# IZU2023_computerboard_ver2.net
KiCad netlist of a schematic drawn in EAGLE
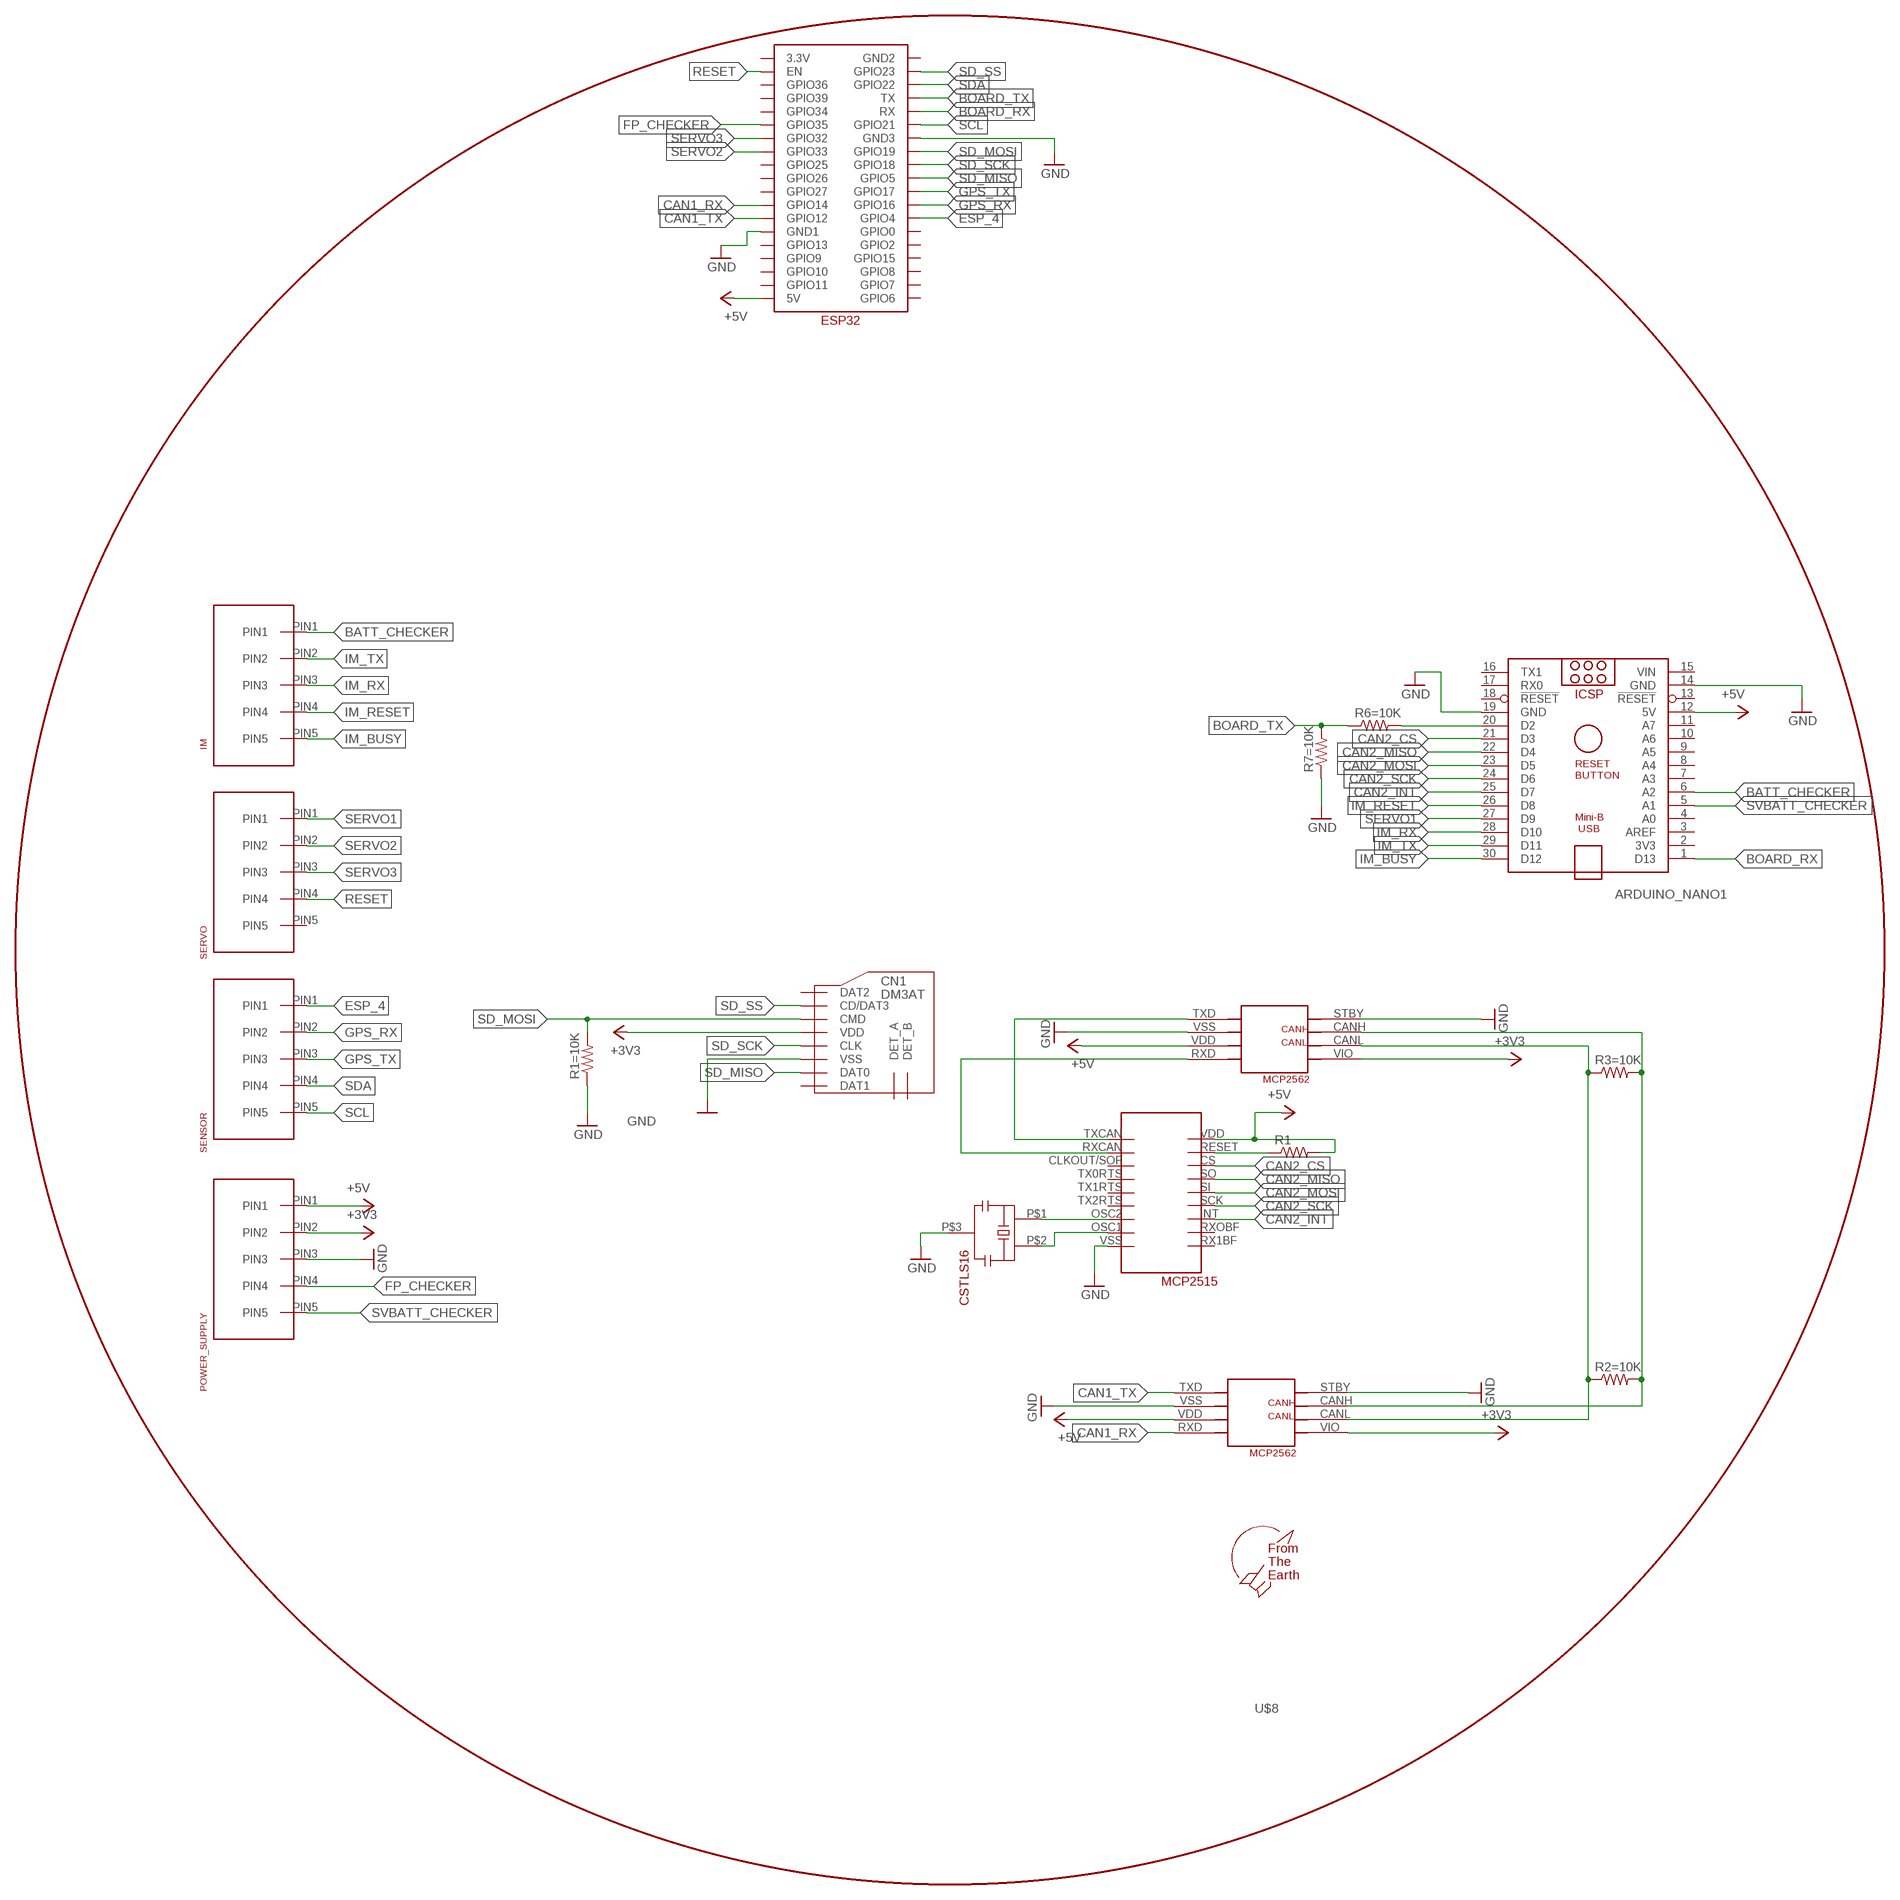
[diagram p0: schematic, sheet 1]

(export (version "E")
  (design (tool "Eeschema 10.0.6"))
  (components
    (comp (ref "ARDUINO_NANO1")
      (value "ARDUINO_NANO")
      (footprint "eagle-import:ARDUINO_NANO")
      (libsource (lib "eagle-import") (part "ARDUINO_NANO"))
    )
    (comp (ref "CN1")
      (value "DM3AT")
      (footprint "eagle-import:DM3AT")
      (libsource (lib "eagle-import") (part "DM3AT"))
    )
    (comp (ref "IM")
      (value "5PIN")
      (footprint "eagle-import:5PIN")
      (libsource (lib "eagle-import") (part "5PIN"))
    )
    (comp (ref "POWER_SUPPLY")
      (value "5PIN")
      (footprint "eagle-import:5PIN")
      (libsource (lib "eagle-import") (part "5PIN"))
    )
    (comp (ref "R1")
      (value "R-US_0204/7")
      (footprint "eagle-import:0204_7")
      (libsource (lib "eagle-import") (part "R-US_0204/7"))
    )
    (comp (ref "R1=10K")
      (value "R-US_0204/7")
      (footprint "eagle-import:0204_7")
      (libsource (lib "eagle-import") (part "R-US_0204/7"))
    )
    (comp (ref "R2=10K")
      (value "R-US_0204/7")
      (footprint "eagle-import:0204_7")
      (libsource (lib "eagle-import") (part "R-US_0204/7"))
    )
    (comp (ref "R3=10K")
      (value "R-US_0204/7")
      (footprint "eagle-import:0204_7")
      (libsource (lib "eagle-import") (part "R-US_0204/7"))
    )
    (comp (ref "R6=10K")
      (value "R-US_0204/7")
      (footprint "eagle-import:0204_7")
      (libsource (lib "eagle-import") (part "R-US_0204/7"))
    )
    (comp (ref "R7=10K")
      (value "R-US_0204/7")
      (footprint "eagle-import:0204_7")
      (libsource (lib "eagle-import") (part "R-US_0204/7"))
    )
    (comp (ref "SENSOR")
      (value "5PIN")
      (footprint "eagle-import:5PIN")
      (libsource (lib "eagle-import") (part "5PIN"))
    )
    (comp (ref "SERVO")
      (value "5PIN")
      (footprint "eagle-import:5PIN")
      (libsource (lib "eagle-import") (part "5PIN"))
    )
    (comp (ref "U$2")
      (value "MCP2515")
      (footprint "eagle-import:MCP2515")
      (libsource (lib "eagle-import") (part "MCP2515"))
    )
    (comp (ref "U$3")
      (value "MCP2562")
      (footprint "eagle-import:MCP2562")
      (libsource (lib "eagle-import") (part "MCP2562"))
    )
    (comp (ref "U$4")
      (value "MCP2562")
      (footprint "eagle-import:MCP2562")
      (libsource (lib "eagle-import") (part "MCP2562"))
    )
    (comp (ref "U$5")
      (value "CSTLS16")
      (footprint "eagle-import:CSTLS16")
      (libsource (lib "eagle-import") (part "CSTLS16"))
    )
    (comp (ref "U$7")
      (value "ESP32_ESP32")
      (footprint "eagle-import:ESP32_ESP32")
      (libsource (lib "eagle-import") (part "ESP32_ESP32"))
    )
    (comp (ref "U$8")
      (value "F.T.E.LOGO")
      (footprint "eagle-import:LOGO")
      (libsource (lib "eagle-import") (part "F.T.E.LOGO"))
    )
  )
  (nets
    (net (code "1") (name "+3V3") (class "Default")
      (node (ref "CN1") (pin "VDD") (pinfunction "VDD_VDD") (pintype "bidirectional"))
      (node (ref "POWER_SUPPLY") (pin "PIN2") (pinfunction "PIN2_PIN2") (pintype "bidirectional"))
      (node (ref "U$3") (pin "VIO") (pinfunction "VIO_VIO") (pintype "bidirectional"))
      (node (ref "U$4") (pin "VIO") (pinfunction "VIO_VIO") (pintype "bidirectional"))
    )
    (net (code "2") (name "+5V") (class "Default")
      (node (ref "ARDUINO_NANO1") (pin "12") (pinfunction "5V_12") (pintype "power_in"))
      (node (ref "POWER_SUPPLY") (pin "PIN1") (pinfunction "PIN1_PIN1") (pintype "bidirectional"))
      (node (ref "R1") (pin "2") (pinfunction "2_2") (pintype "passive"))
      (node (ref "U$2") (pin "VDD") (pinfunction "VDD_VDD") (pintype "bidirectional"))
      (node (ref "U$3") (pin "VDD") (pinfunction "VDD_VDD") (pintype "bidirectional"))
      (node (ref "U$4") (pin "VDD") (pinfunction "VDD_VDD") (pintype "bidirectional"))
      (node (ref "U$7") (pin "5V") (pinfunction "5V_5V") (pintype "bidirectional"))
    )
    (net (code "3") (name "/VIN") (class "Default")
      (node (ref "ARDUINO_NANO1") (pin "15") (pinfunction "VIN_15") (pintype "power_in"))
    )
    (net (code "4") (name "BATT_CHECKER") (class "Default")
      (node (ref "ARDUINO_NANO1") (pin "6") (pinfunction "A2_6") (pintype "bidirectional"))
      (node (ref "IM") (pin "PIN1") (pinfunction "PIN1_PIN1") (pintype "bidirectional"))
    )
    (net (code "5") (name "BOARD_RX") (class "Default")
      (node (ref "ARDUINO_NANO1") (pin "1") (pinfunction "D13_1") (pintype "bidirectional"))
      (node (ref "U$7") (pin "RX") (pinfunction "RX_RX") (pintype "bidirectional"))
    )
    (net (code "6") (name "BOARD_TX") (class "Default")
      (node (ref "R6=10K") (pin "1") (pinfunction "1_1") (pintype "passive"))
      (node (ref "R7=10K") (pin "2") (pinfunction "2_2") (pintype "passive"))
      (node (ref "U$7") (pin "TX") (pinfunction "TX_TX") (pintype "bidirectional"))
    )
    (net (code "7") (name "CAN1_RX") (class "Default")
      (node (ref "U$3") (pin "RXD") (pinfunction "RXD_RXD") (pintype "bidirectional"))
      (node (ref "U$7") (pin "GPIO14") (pinfunction "GPIO14_GPIO14") (pintype "bidirectional"))
    )
    (net (code "8") (name "CAN1_TX") (class "Default")
      (node (ref "U$3") (pin "TXD") (pinfunction "TXD_TXD") (pintype "bidirectional"))
      (node (ref "U$7") (pin "GPIO12") (pinfunction "GPIO12_GPIO12") (pintype "bidirectional"))
    )
    (net (code "9") (name "CAN2_CS") (class "Default")
      (node (ref "ARDUINO_NANO1") (pin "21") (pinfunction "D3_21") (pintype "bidirectional"))
      (node (ref "U$2") (pin "CS") (pinfunction "CS_CS") (pintype "bidirectional"))
    )
    (net (code "10") (name "CAN2_INT") (class "Default")
      (node (ref "ARDUINO_NANO1") (pin "25") (pinfunction "D7_25") (pintype "bidirectional"))
      (node (ref "U$2") (pin "INT") (pinfunction "INT_INT") (pintype "bidirectional"))
    )
    (net (code "11") (name "CAN2_MISO") (class "Default")
      (node (ref "ARDUINO_NANO1") (pin "22") (pinfunction "D4_22") (pintype "bidirectional"))
      (node (ref "U$2") (pin "SO") (pinfunction "SO_SO") (pintype "bidirectional"))
    )
    (net (code "12") (name "CAN2_MOSI") (class "Default")
      (node (ref "ARDUINO_NANO1") (pin "23") (pinfunction "D5_23") (pintype "bidirectional"))
      (node (ref "U$2") (pin "SI") (pinfunction "SI_SI") (pintype "bidirectional"))
    )
    (net (code "13") (name "CAN2_SCK") (class "Default")
      (node (ref "ARDUINO_NANO1") (pin "24") (pinfunction "D6_24") (pintype "bidirectional"))
      (node (ref "U$2") (pin "SCK") (pinfunction "SCK_SCK") (pintype "bidirectional"))
    )
    (net (code "14") (name "ESP_4") (class "Default")
      (node (ref "SENSOR") (pin "PIN1") (pinfunction "PIN1_PIN1") (pintype "bidirectional"))
      (node (ref "U$7") (pin "GPIO4") (pinfunction "GPIO4_GPIO4") (pintype "bidirectional"))
    )
    (net (code "15") (name "FP_CHECKER") (class "Default")
      (node (ref "POWER_SUPPLY") (pin "PIN4") (pinfunction "PIN4_PIN4") (pintype "bidirectional"))
      (node (ref "U$7") (pin "GPIO35") (pinfunction "GPIO35_GPIO35") (pintype "bidirectional"))
    )
    (net (code "16") (name "GND") (class "Default")
      (node (ref "ARDUINO_NANO1") (pin "14") (pinfunction "GND_14") (pintype "power_in"))
      (node (ref "ARDUINO_NANO1") (pin "19") (pinfunction "GND_19") (pintype "power_in"))
      (node (ref "CN1") (pin "VSS") (pinfunction "VSS_VSS") (pintype "bidirectional"))
      (node (ref "POWER_SUPPLY") (pin "PIN3") (pinfunction "PIN3_PIN3") (pintype "bidirectional"))
      (node (ref "R1=10K") (pin "1") (pinfunction "1_1") (pintype "passive"))
      (node (ref "R7=10K") (pin "1") (pinfunction "1_1") (pintype "passive"))
      (node (ref "U$2") (pin "VSS") (pinfunction "VSS_VSS") (pintype "bidirectional"))
      (node (ref "U$3") (pin "STBY") (pinfunction "STBY_STBY") (pintype "bidirectional"))
      (node (ref "U$3") (pin "VSS") (pinfunction "VSS_VSS") (pintype "bidirectional"))
      (node (ref "U$4") (pin "STBY") (pinfunction "STBY_STBY") (pintype "bidirectional"))
      (node (ref "U$4") (pin "VSS") (pinfunction "VSS_VSS") (pintype "bidirectional"))
      (node (ref "U$5") (pin "P$3") (pinfunction "P$3_P$3") (pintype "bidirectional"))
      (node (ref "U$7") (pin "GND1") (pinfunction "GND1_GND1") (pintype "bidirectional"))
      (node (ref "U$7") (pin "GND3") (pinfunction "GND3_GND3") (pintype "bidirectional"))
    )
    (net (code "17") (name "GPS_RX") (class "Default")
      (node (ref "SENSOR") (pin "PIN2") (pinfunction "PIN2_PIN2") (pintype "bidirectional"))
      (node (ref "U$7") (pin "GPIO16") (pinfunction "GPIO16_GPIO16") (pintype "bidirectional"))
    )
    (net (code "18") (name "GPS_TX") (class "Default")
      (node (ref "SENSOR") (pin "PIN3") (pinfunction "PIN3_PIN3") (pintype "bidirectional"))
      (node (ref "U$7") (pin "GPIO17") (pinfunction "GPIO17_GPIO17") (pintype "bidirectional"))
    )
    (net (code "19") (name "IM_BUSY") (class "Default")
      (node (ref "ARDUINO_NANO1") (pin "30") (pinfunction "D12_30") (pintype "bidirectional"))
      (node (ref "IM") (pin "PIN5") (pinfunction "PIN5_PIN5") (pintype "bidirectional"))
    )
    (net (code "20") (name "IM_RESET") (class "Default")
      (node (ref "ARDUINO_NANO1") (pin "26") (pinfunction "D8_26") (pintype "bidirectional"))
      (node (ref "IM") (pin "PIN4") (pinfunction "PIN4_PIN4") (pintype "bidirectional"))
    )
    (net (code "21") (name "IM_RX") (class "Default")
      (node (ref "ARDUINO_NANO1") (pin "28") (pinfunction "D10_28") (pintype "bidirectional"))
      (node (ref "IM") (pin "PIN3") (pinfunction "PIN3_PIN3") (pintype "bidirectional"))
    )
    (net (code "22") (name "IM_TX") (class "Default")
      (node (ref "ARDUINO_NANO1") (pin "29") (pinfunction "D11_29") (pintype "bidirectional"))
      (node (ref "IM") (pin "PIN2") (pinfunction "PIN2_PIN2") (pintype "bidirectional"))
    )
    (net (code "23") (name "Net-(ARDUINO_NANO1-D2)") (class "Default")
      (node (ref "ARDUINO_NANO1") (pin "20") (pinfunction "D2_20") (pintype "bidirectional"))
      (node (ref "R6=10K") (pin "2") (pinfunction "2_2") (pintype "passive"))
    )
    (net (code "24") (name "Net-(R1-Pad1)") (class "Default")
      (node (ref "R1") (pin "1") (pinfunction "1_1") (pintype "passive"))
      (node (ref "U$2") (pin "RESET") (pinfunction "RESET_RESET") (pintype "bidirectional"))
    )
    (net (code "25") (name "Net-(R2=10K-Pad1)") (class "Default")
      (node (ref "R2=10K") (pin "1") (pinfunction "1_1") (pintype "passive"))
      (node (ref "R3=10K") (pin "1") (pinfunction "1_1") (pintype "passive"))
      (node (ref "U$3") (pin "CANL") (pinfunction "CANL_CANL") (pintype "bidirectional"))
      (node (ref "U$4") (pin "CANL") (pinfunction "CANL_CANL") (pintype "bidirectional"))
    )
    (net (code "26") (name "Net-(R2=10K-Pad2)") (class "Default")
      (node (ref "R2=10K") (pin "2") (pinfunction "2_2") (pintype "passive"))
      (node (ref "R3=10K") (pin "2") (pinfunction "2_2") (pintype "passive"))
      (node (ref "U$3") (pin "CANH") (pinfunction "CANH_CANH") (pintype "bidirectional"))
      (node (ref "U$4") (pin "CANH") (pinfunction "CANH_CANH") (pintype "bidirectional"))
    )
    (net (code "27") (name "Net-(U$2-PadOSC1)") (class "Default")
      (node (ref "U$2") (pin "OSC1") (pinfunction "OSC1_OSC1") (pintype "bidirectional"))
      (node (ref "U$5") (pin "P$2") (pinfunction "P$2_P$2") (pintype "bidirectional"))
    )
    (net (code "28") (name "Net-(U$2-PadOSC2)") (class "Default")
      (node (ref "U$2") (pin "OSC2") (pinfunction "OSC2_OSC2") (pintype "bidirectional"))
      (node (ref "U$5") (pin "P$1") (pinfunction "P$1_P$1") (pintype "bidirectional"))
    )
    (net (code "29") (name "Net-(U$2-PadRXCAN)") (class "Default")
      (node (ref "U$2") (pin "RXCAN") (pinfunction "RXCAN_RXCAN") (pintype "bidirectional"))
      (node (ref "U$4") (pin "RXD") (pinfunction "RXD_RXD") (pintype "bidirectional"))
    )
    (net (code "30") (name "Net-(U$2-PadTXCAN)") (class "Default")
      (node (ref "U$2") (pin "TXCAN") (pinfunction "TXCAN_TXCAN") (pintype "bidirectional"))
      (node (ref "U$4") (pin "TXD") (pinfunction "TXD_TXD") (pintype "bidirectional"))
    )
    (net (code "31") (name "RESET") (class "Default")
      (node (ref "SERVO") (pin "PIN4") (pinfunction "PIN4_PIN4") (pintype "bidirectional"))
      (node (ref "U$7") (pin "EN") (pinfunction "EN_EN") (pintype "bidirectional"))
    )
    (net (code "32") (name "SCL") (class "Default")
      (node (ref "SENSOR") (pin "PIN5") (pinfunction "PIN5_PIN5") (pintype "bidirectional"))
      (node (ref "U$7") (pin "GPIO21") (pinfunction "GPIO21_GPIO21") (pintype "bidirectional"))
    )
    (net (code "33") (name "SDA") (class "Default")
      (node (ref "SENSOR") (pin "PIN4") (pinfunction "PIN4_PIN4") (pintype "bidirectional"))
      (node (ref "U$7") (pin "GPIO22") (pinfunction "GPIO22_GPIO22") (pintype "bidirectional"))
    )
    (net (code "34") (name "SD_MISO") (class "Default")
      (node (ref "CN1") (pin "DAT0") (pinfunction "DAT0_DAT0") (pintype "bidirectional"))
      (node (ref "U$7") (pin "GPIO5") (pinfunction "GPIO5_GPIO5") (pintype "bidirectional"))
    )
    (net (code "35") (name "SD_MOSI") (class "Default")
      (node (ref "CN1") (pin "CMD") (pinfunction "CMD_CMD") (pintype "bidirectional"))
      (node (ref "R1=10K") (pin "2") (pinfunction "2_2") (pintype "passive"))
      (node (ref "U$7") (pin "GPIO19") (pinfunction "GPIO19_GPIO19") (pintype "bidirectional"))
    )
    (net (code "36") (name "SD_SCK") (class "Default")
      (node (ref "CN1") (pin "CLK") (pinfunction "CLK_CLK") (pintype "bidirectional"))
      (node (ref "U$7") (pin "GPIO18") (pinfunction "GPIO18_GPIO18") (pintype "bidirectional"))
    )
    (net (code "37") (name "SD_SS") (class "Default")
      (node (ref "CN1") (pin "CD/DAT3") (pinfunction "CD/DAT3_CD/DAT3") (pintype "bidirectional"))
      (node (ref "U$7") (pin "GPIO23") (pinfunction "GPIO23_GPIO23") (pintype "bidirectional"))
    )
    (net (code "38") (name "SERVO1") (class "Default")
      (node (ref "ARDUINO_NANO1") (pin "27") (pinfunction "D9_27") (pintype "bidirectional"))
      (node (ref "SERVO") (pin "PIN1") (pinfunction "PIN1_PIN1") (pintype "bidirectional"))
    )
    (net (code "39") (name "SERVO2") (class "Default")
      (node (ref "SERVO") (pin "PIN2") (pinfunction "PIN2_PIN2") (pintype "bidirectional"))
      (node (ref "U$7") (pin "GPIO33") (pinfunction "GPIO33_GPIO33") (pintype "bidirectional"))
    )
    (net (code "40") (name "SERVO3") (class "Default")
      (node (ref "SERVO") (pin "PIN3") (pinfunction "PIN3_PIN3") (pintype "bidirectional"))
      (node (ref "U$7") (pin "GPIO32") (pinfunction "GPIO32_GPIO32") (pintype "bidirectional"))
    )
    (net (code "41") (name "SVBATT_CHECKER") (class "Default")
      (node (ref "ARDUINO_NANO1") (pin "5") (pinfunction "A1_5") (pintype "bidirectional"))
      (node (ref "POWER_SUPPLY") (pin "PIN5") (pinfunction "PIN5_PIN5") (pintype "bidirectional"))
    )
    (net (code "42") (name "unconnected-(ARDUINO_NANO1-3V3-Pad2)") (class "Default")
      (node (ref "ARDUINO_NANO1") (pin "2") (pinfunction "3V3_2") (pintype "output"))
    )
    (net (code "43") (name "unconnected-(ARDUINO_NANO1-A0-Pad4)") (class "Default")
      (node (ref "ARDUINO_NANO1") (pin "4") (pinfunction "A0_4") (pintype "bidirectional"))
    )
    (net (code "44") (name "unconnected-(ARDUINO_NANO1-A3-Pad7)") (class "Default")
      (node (ref "ARDUINO_NANO1") (pin "7") (pinfunction "A3_7") (pintype "bidirectional"))
    )
    (net (code "45") (name "unconnected-(ARDUINO_NANO1-A4-Pad8)") (class "Default")
      (node (ref "ARDUINO_NANO1") (pin "8") (pinfunction "A4_8") (pintype "bidirectional"))
    )
    (net (code "46") (name "unconnected-(ARDUINO_NANO1-A5-Pad9)") (class "Default")
      (node (ref "ARDUINO_NANO1") (pin "9") (pinfunction "A5_9") (pintype "bidirectional"))
    )
    (net (code "47") (name "unconnected-(ARDUINO_NANO1-A6-Pad10)") (class "Default")
      (node (ref "ARDUINO_NANO1") (pin "10") (pinfunction "A6_10") (pintype "bidirectional"))
    )
    (net (code "48") (name "unconnected-(ARDUINO_NANO1-A7-Pad11)") (class "Default")
      (node (ref "ARDUINO_NANO1") (pin "11") (pinfunction "A7_11") (pintype "bidirectional"))
    )
    (net (code "49") (name "unconnected-(ARDUINO_NANO1-AREF-Pad3)") (class "Default")
      (node (ref "ARDUINO_NANO1") (pin "3") (pinfunction "AREF_3") (pintype "input"))
    )
    (net (code "50") (name "unconnected-(ARDUINO_NANO1-RX0-Pad17)") (class "Default")
      (node (ref "ARDUINO_NANO1") (pin "17") (pinfunction "RX0_17") (pintype "bidirectional"))
    )
    (net (code "51") (name "unconnected-(ARDUINO_NANO1-TX1-Pad16)") (class "Default")
      (node (ref "ARDUINO_NANO1") (pin "16") (pinfunction "TX1_16") (pintype "bidirectional"))
    )
    (net (code "52") (name "unconnected-(ARDUINO_NANO1-~{RESET}-Pad13)") (class "Default")
      (node (ref "ARDUINO_NANO1") (pin "13") (pinfunction "~{RESET}_13") (pintype "input"))
    )
    (net (code "53") (name "unconnected-(ARDUINO_NANO1-~{RESET}-Pad18)") (class "Default")
      (node (ref "ARDUINO_NANO1") (pin "18") (pinfunction "~{RESET}_18") (pintype "input"))
    )
    (net (code "54") (name "unconnected-(CN1-PadDAT1)") (class "Default")
      (node (ref "CN1") (pin "DAT1") (pinfunction "DAT1_DAT1") (pintype "bidirectional"))
    )
    (net (code "55") (name "unconnected-(CN1-PadDAT2)") (class "Default")
      (node (ref "CN1") (pin "DAT2") (pinfunction "DAT2_DAT2") (pintype "bidirectional"))
    )
    (net (code "56") (name "unconnected-(CN1-PadDET_A)") (class "Default")
      (node (ref "CN1") (pin "DET_A") (pinfunction "DET_A_DET_A") (pintype "bidirectional"))
    )
    (net (code "57") (name "unconnected-(CN1-PadDET_B)") (class "Default")
      (node (ref "CN1") (pin "DET_B") (pinfunction "DET_B_DET_B") (pintype "bidirectional"))
    )
    (net (code "58") (name "unconnected-(SERVO-PadPIN5)") (class "Default")
      (node (ref "SERVO") (pin "PIN5") (pinfunction "PIN5_PIN5") (pintype "bidirectional"))
    )
    (net (code "59") (name "unconnected-(U$2-PadCLKOUT{slash}SOF)") (class "Default")
      (node (ref "U$2") (pin "CLKOUT/SOF") (pinfunction "CLKOUT/SOF_CLKOUT/SOF") (pintype "bidirectional"))
    )
    (net (code "60") (name "unconnected-(U$2-PadRX1BF)") (class "Default")
      (node (ref "U$2") (pin "RX1BF") (pinfunction "RX1BF_RX1BF") (pintype "bidirectional"))
    )
    (net (code "61") (name "unconnected-(U$2-PadTX0RTS)") (class "Default")
      (node (ref "U$2") (pin "TX0RTS") (pinfunction "TX0RTS_TX0RTS") (pintype "bidirectional"))
    )
    (net (code "62") (name "unconnected-(U$2-PadTX1RTS)") (class "Default")
      (node (ref "U$2") (pin "TX1RTS") (pinfunction "TX1RTS_TX1RTS") (pintype "bidirectional"))
    )
    (net (code "63") (name "unconnected-(U$2-PadTX2RTS)") (class "Default")
      (node (ref "U$2") (pin "TX2RTS") (pinfunction "TX2RTS_TX2RTS") (pintype "bidirectional"))
    )
    (net (code "64") (name "unconnected-(U$2-RX0BF-PadRXOBF)") (class "Default")
      (node (ref "U$2") (pin "RXOBF") (pinfunction "RX0BF_RXOBF") (pintype "bidirectional"))
    )
    (net (code "65") (name "unconnected-(U$7-Pad3.3V)") (class "Default")
      (node (ref "U$7") (pin "3.3V") (pinfunction "3.3V_3.3V") (pintype "bidirectional"))
    )
    (net (code "66") (name "unconnected-(U$7-PadGND2)") (class "Default")
      (node (ref "U$7") (pin "GND2") (pinfunction "GND2_GND2") (pintype "bidirectional"))
    )
    (net (code "67") (name "unconnected-(U$7-PadGPIO0)") (class "Default")
      (node (ref "U$7") (pin "GPIO0") (pinfunction "GPIO0_GPIO0") (pintype "bidirectional"))
    )
    (net (code "68") (name "unconnected-(U$7-PadGPIO2)") (class "Default")
      (node (ref "U$7") (pin "GPIO2") (pinfunction "GPIO2_GPIO2") (pintype "bidirectional"))
    )
    (net (code "69") (name "unconnected-(U$7-PadGPIO6)") (class "Default")
      (node (ref "U$7") (pin "GPIO6") (pinfunction "GPIO6_GPIO6") (pintype "bidirectional"))
    )
    (net (code "70") (name "unconnected-(U$7-PadGPIO7)") (class "Default")
      (node (ref "U$7") (pin "GPIO7") (pinfunction "GPIO7_GPIO7") (pintype "bidirectional"))
    )
    (net (code "71") (name "unconnected-(U$7-PadGPIO8)") (class "Default")
      (node (ref "U$7") (pin "GPIO8") (pinfunction "GPIO8_GPIO8") (pintype "bidirectional"))
    )
    (net (code "72") (name "unconnected-(U$7-PadGPIO9)") (class "Default")
      (node (ref "U$7") (pin "GPIO9") (pinfunction "GPIO9_GPIO9") (pintype "bidirectional"))
    )
    (net (code "73") (name "unconnected-(U$7-PadGPIO10)") (class "Default")
      (node (ref "U$7") (pin "GPIO10") (pinfunction "GPIO10_GPIO10") (pintype "bidirectional"))
    )
    (net (code "74") (name "unconnected-(U$7-PadGPIO11)") (class "Default")
      (node (ref "U$7") (pin "GPIO11") (pinfunction "GPIO11_GPIO11") (pintype "bidirectional"))
    )
    (net (code "75") (name "unconnected-(U$7-PadGPIO13)") (class "Default")
      (node (ref "U$7") (pin "GPIO13") (pinfunction "GPIO13_GPIO13") (pintype "bidirectional"))
    )
    (net (code "76") (name "unconnected-(U$7-PadGPIO15)") (class "Default")
      (node (ref "U$7") (pin "GPIO15") (pinfunction "GPIO15_GPIO15") (pintype "bidirectional"))
    )
    (net (code "77") (name "unconnected-(U$7-PadGPIO25)") (class "Default")
      (node (ref "U$7") (pin "GPIO25") (pinfunction "GPIO25_GPIO25") (pintype "bidirectional"))
    )
    (net (code "78") (name "unconnected-(U$7-PadGPIO26)") (class "Default")
      (node (ref "U$7") (pin "GPIO26") (pinfunction "GPIO26_GPIO26") (pintype "bidirectional"))
    )
    (net (code "79") (name "unconnected-(U$7-PadGPIO27)") (class "Default")
      (node (ref "U$7") (pin "GPIO27") (pinfunction "GPIO27_GPIO27") (pintype "bidirectional"))
    )
    (net (code "80") (name "unconnected-(U$7-PadGPIO34)") (class "Default")
      (node (ref "U$7") (pin "GPIO34") (pinfunction "GPIO34_GPIO34") (pintype "bidirectional"))
    )
    (net (code "81") (name "unconnected-(U$7-PadGPIO36)") (class "Default")
      (node (ref "U$7") (pin "GPIO36") (pinfunction "GPIO36_GPIO36") (pintype "bidirectional"))
    )
    (net (code "82") (name "unconnected-(U$7-PadGPIO39)") (class "Default")
      (node (ref "U$7") (pin "GPIO39") (pinfunction "GPIO39_GPIO39") (pintype "bidirectional"))
    )
  )
)
